# 6_MUX.net
KiCad netlist of a schematic drawn in Altium Designer
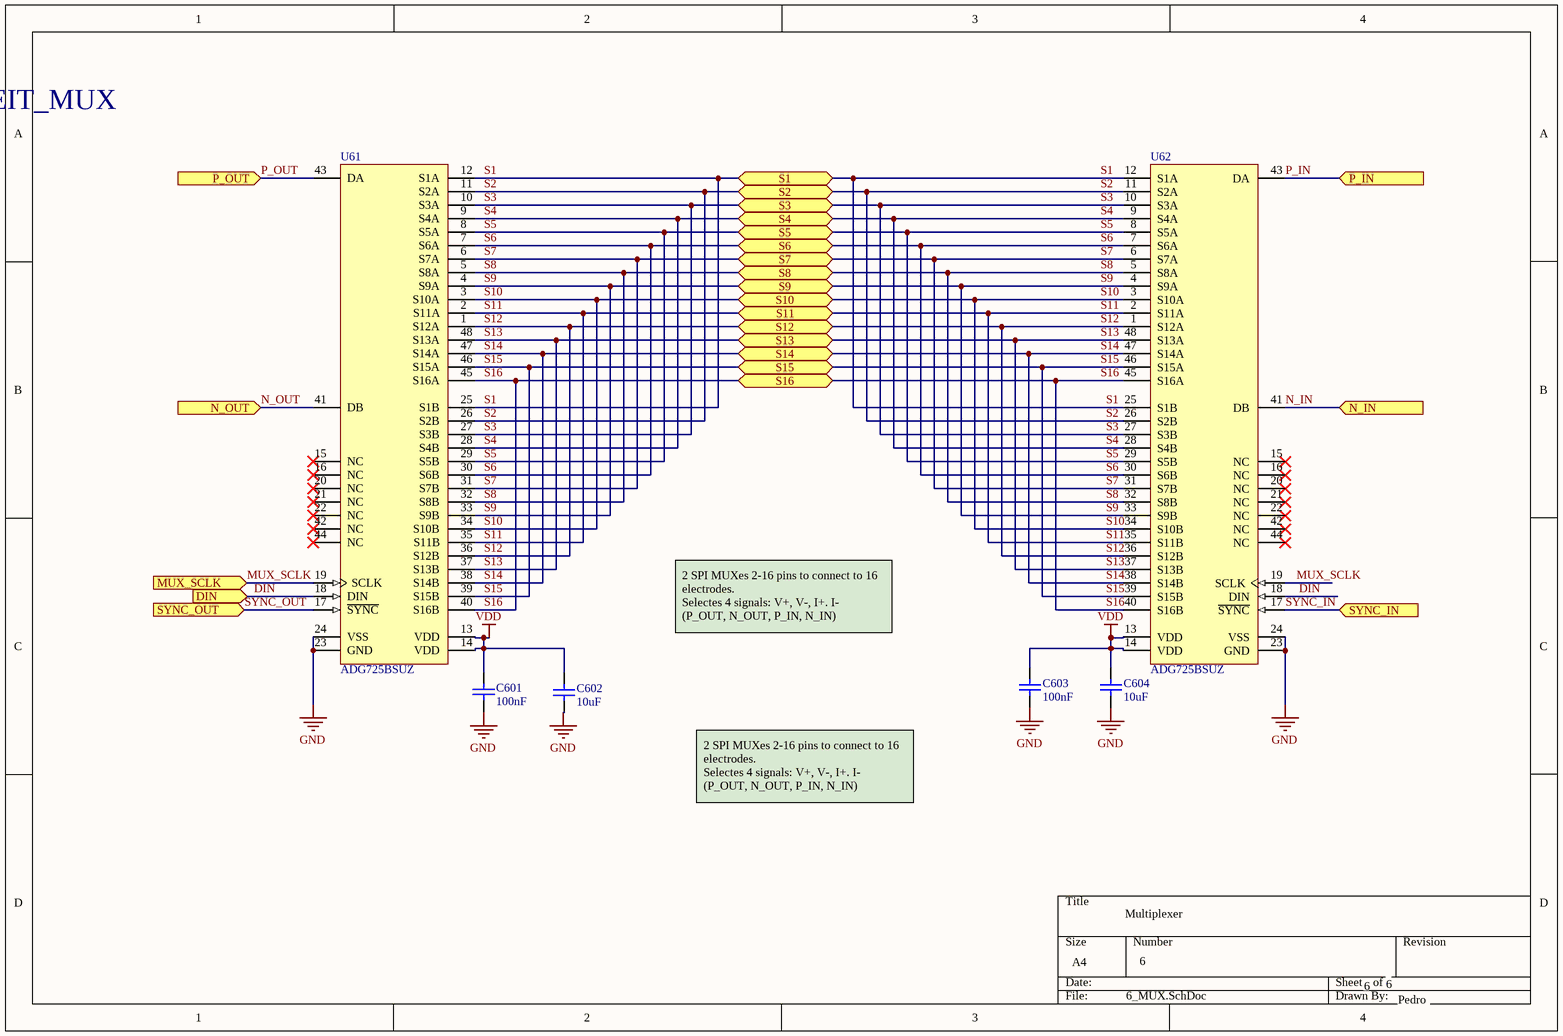
[diagram p0: 6_MUX.SchDoc]

(export (version "E")
  (design (tool "Eeschema 10.0.6"))
  (components
    (comp (ref "C601")
      (value "100nF")
      (footprint "CAPC1005X55X30LL05T10")
      (description "generic")
      (libsource (lib "RPI_EIT_SchLib") (part "Capacitor"))
    )
    (comp (ref "C602")
      (value "10uF")
      (footprint "FP-C0603C-CF-IPC_A")
      (description "generic")
      (libsource (lib "RPI_EIT_SchLib") (part "Capacitor"))
    )
    (comp (ref "C603")
      (value "100nF")
      (footprint "CAPC1005X55X30LL05T10")
      (description "generic")
      (libsource (lib "RPI_EIT_SchLib") (part "Capacitor"))
    )
    (comp (ref "C604")
      (value "10uF")
      (footprint "FP-C0603C-CF-IPC_A")
      (description "generic")
      (libsource (lib "RPI_EIT_SchLib") (part "Capacitor"))
    )
    (comp (ref "U61")
      (value "ADG725BSUZ")
      (footprint "ADI-SU-48_N")
      (fields (field (name "MANUFACTURER") "Analog Devices"))
      (libsource (lib "RPI_EIT_SchLib") (part "ADI-ADG725-SU-48"))
    )
    (comp (ref "U62")
      (value "ADG725BSUZ")
      (footprint "ADI-SU-48_N")
      (fields (field (name "MANUFACTURER") "Analog Devices"))
      (libsource (lib "") (part "ADI-ADG725-SU-48_1"))
    )
  )
  (nets
    (net (code "1") (name "/DIN") (class "Default")
      (node (ref "U61") (pin "18") (pinfunction "DIN_18") (pintype "input"))
      (node (ref "U62") (pin "18") (pinfunction "DIN_18") (pintype "input"))
    )
    (net (code "2") (name "/MUX_SCLK") (class "Default")
      (node (ref "U61") (pin "19") (pinfunction "SCLK_19") (pintype "input"))
      (node (ref "U62") (pin "19") (pinfunction "SCLK_19") (pintype "input"))
    )
    (net (code "3") (name "/N_IN") (class "Default")
      (node (ref "U62") (pin "41") (pinfunction "DB_41") (pintype "passive"))
    )
    (net (code "4") (name "/N_OUT") (class "Default")
      (node (ref "U61") (pin "41") (pinfunction "DB_41") (pintype "passive"))
    )
    (net (code "5") (name "/P_IN") (class "Default")
      (node (ref "U62") (pin "43") (pinfunction "DA_43") (pintype "passive"))
    )
    (net (code "6") (name "/P_OUT") (class "Default")
      (node (ref "U61") (pin "43") (pinfunction "DA_43") (pintype "passive"))
    )
    (net (code "7") (name "/S1") (class "Default")
      (node (ref "U61") (pin "12") (pinfunction "S1A_12") (pintype "passive"))
      (node (ref "U61") (pin "25") (pinfunction "S1B_25") (pintype "passive"))
      (node (ref "U62") (pin "12") (pinfunction "S1A_12") (pintype "passive"))
      (node (ref "U62") (pin "25") (pinfunction "S1B_25") (pintype "passive"))
    )
    (net (code "8") (name "/S2") (class "Default")
      (node (ref "U61") (pin "11") (pinfunction "S2A_11") (pintype "passive"))
      (node (ref "U61") (pin "26") (pinfunction "S2B_26") (pintype "passive"))
      (node (ref "U62") (pin "11") (pinfunction "S2A_11") (pintype "passive"))
      (node (ref "U62") (pin "26") (pinfunction "S2B_26") (pintype "passive"))
    )
    (net (code "9") (name "/S3") (class "Default")
      (node (ref "U61") (pin "10") (pinfunction "S3A_10") (pintype "passive"))
      (node (ref "U61") (pin "27") (pinfunction "S3B_27") (pintype "passive"))
      (node (ref "U62") (pin "10") (pinfunction "S3A_10") (pintype "passive"))
      (node (ref "U62") (pin "27") (pinfunction "S3B_27") (pintype "passive"))
    )
    (net (code "10") (name "/S4") (class "Default")
      (node (ref "U61") (pin "28") (pinfunction "S4B_28") (pintype "passive"))
      (node (ref "U61") (pin "9") (pinfunction "S4A_9") (pintype "passive"))
      (node (ref "U62") (pin "28") (pinfunction "S4B_28") (pintype "passive"))
      (node (ref "U62") (pin "9") (pinfunction "S4A_9") (pintype "passive"))
    )
    (net (code "11") (name "/S5") (class "Default")
      (node (ref "U61") (pin "29") (pinfunction "S5B_29") (pintype "passive"))
      (node (ref "U61") (pin "8") (pinfunction "S5A_8") (pintype "passive"))
      (node (ref "U62") (pin "29") (pinfunction "S5B_29") (pintype "passive"))
      (node (ref "U62") (pin "8") (pinfunction "S5A_8") (pintype "passive"))
    )
    (net (code "12") (name "/S6") (class "Default")
      (node (ref "U61") (pin "30") (pinfunction "S6B_30") (pintype "passive"))
      (node (ref "U61") (pin "7") (pinfunction "S6A_7") (pintype "passive"))
      (node (ref "U62") (pin "30") (pinfunction "S6B_30") (pintype "passive"))
      (node (ref "U62") (pin "7") (pinfunction "S6A_7") (pintype "passive"))
    )
    (net (code "13") (name "/S7") (class "Default")
      (node (ref "U61") (pin "31") (pinfunction "S7B_31") (pintype "passive"))
      (node (ref "U61") (pin "6") (pinfunction "S7A_6") (pintype "passive"))
      (node (ref "U62") (pin "31") (pinfunction "S7B_31") (pintype "passive"))
      (node (ref "U62") (pin "6") (pinfunction "S7A_6") (pintype "passive"))
    )
    (net (code "14") (name "/S8") (class "Default")
      (node (ref "U61") (pin "32") (pinfunction "S8B_32") (pintype "passive"))
      (node (ref "U61") (pin "5") (pinfunction "S8A_5") (pintype "passive"))
      (node (ref "U62") (pin "32") (pinfunction "S8B_32") (pintype "passive"))
      (node (ref "U62") (pin "5") (pinfunction "S8A_5") (pintype "passive"))
    )
    (net (code "15") (name "/S9") (class "Default")
      (node (ref "U61") (pin "33") (pinfunction "S9B_33") (pintype "passive"))
      (node (ref "U61") (pin "4") (pinfunction "S9A_4") (pintype "passive"))
      (node (ref "U62") (pin "33") (pinfunction "S9B_33") (pintype "passive"))
      (node (ref "U62") (pin "4") (pinfunction "S9A_4") (pintype "passive"))
    )
    (net (code "16") (name "/S10") (class "Default")
      (node (ref "U61") (pin "3") (pinfunction "S10A_3") (pintype "passive"))
      (node (ref "U61") (pin "34") (pinfunction "S10B_34") (pintype "passive"))
      (node (ref "U62") (pin "3") (pinfunction "S10A_3") (pintype "passive"))
      (node (ref "U62") (pin "34") (pinfunction "S10B_34") (pintype "passive"))
    )
    (net (code "17") (name "/S11") (class "Default")
      (node (ref "U61") (pin "2") (pinfunction "S11A_2") (pintype "passive"))
      (node (ref "U61") (pin "35") (pinfunction "S11B_35") (pintype "passive"))
      (node (ref "U62") (pin "2") (pinfunction "S11A_2") (pintype "passive"))
      (node (ref "U62") (pin "35") (pinfunction "S11B_35") (pintype "passive"))
    )
    (net (code "18") (name "/S12") (class "Default")
      (node (ref "U61") (pin "1") (pinfunction "S12A_1") (pintype "passive"))
      (node (ref "U61") (pin "36") (pinfunction "S12B_36") (pintype "passive"))
      (node (ref "U62") (pin "1") (pinfunction "S12A_1") (pintype "passive"))
      (node (ref "U62") (pin "36") (pinfunction "S12B_36") (pintype "passive"))
    )
    (net (code "19") (name "/S13") (class "Default")
      (node (ref "U61") (pin "37") (pinfunction "S13B_37") (pintype "passive"))
      (node (ref "U61") (pin "48") (pinfunction "S13A_48") (pintype "passive"))
      (node (ref "U62") (pin "37") (pinfunction "S13B_37") (pintype "passive"))
      (node (ref "U62") (pin "48") (pinfunction "S13A_48") (pintype "passive"))
    )
    (net (code "20") (name "/S14") (class "Default")
      (node (ref "U61") (pin "38") (pinfunction "S14B_38") (pintype "passive"))
      (node (ref "U61") (pin "47") (pinfunction "S14A_47") (pintype "passive"))
      (node (ref "U62") (pin "38") (pinfunction "S14B_38") (pintype "passive"))
      (node (ref "U62") (pin "47") (pinfunction "S14A_47") (pintype "passive"))
    )
    (net (code "21") (name "/S15") (class "Default")
      (node (ref "U61") (pin "39") (pinfunction "S15B_39") (pintype "passive"))
      (node (ref "U61") (pin "46") (pinfunction "S15A_46") (pintype "passive"))
      (node (ref "U62") (pin "39") (pinfunction "S15B_39") (pintype "passive"))
      (node (ref "U62") (pin "46") (pinfunction "S15A_46") (pintype "passive"))
    )
    (net (code "22") (name "/S16") (class "Default")
      (node (ref "U61") (pin "40") (pinfunction "S16B_40") (pintype "passive"))
      (node (ref "U61") (pin "45") (pinfunction "S16A_45") (pintype "passive"))
      (node (ref "U62") (pin "40") (pinfunction "S16B_40") (pintype "passive"))
      (node (ref "U62") (pin "45") (pinfunction "S16A_45") (pintype "passive"))
    )
    (net (code "23") (name "/SYNC_IN") (class "Default")
      (node (ref "U62") (pin "17") (pinfunction "~{SYNC}_17") (pintype "input"))
    )
    (net (code "24") (name "/SYNC_OUT") (class "Default")
      (node (ref "U61") (pin "17") (pinfunction "~{SYNC}_17") (pintype "input"))
    )
    (net (code "25") (name "GND") (class "Default")
      (node (ref "C601") (pin "2") (pinfunction "2_2") (pintype "passive"))
      (node (ref "C602") (pin "2") (pinfunction "2_2") (pintype "passive"))
      (node (ref "C603") (pin "2") (pinfunction "2_2") (pintype "passive"))
      (node (ref "C604") (pin "2") (pinfunction "2_2") (pintype "passive"))
      (node (ref "U61") (pin "23") (pinfunction "GND_23") (pintype "power_in"))
      (node (ref "U61") (pin "24") (pinfunction "VSS_24") (pintype "power_in"))
      (node (ref "U62") (pin "23") (pinfunction "GND_23") (pintype "power_in"))
      (node (ref "U62") (pin "24") (pinfunction "VSS_24") (pintype "power_in"))
    )
    (net (code "26") (name "VDD") (class "Default")
      (node (ref "C601") (pin "1") (pinfunction "1_1") (pintype "passive"))
      (node (ref "C602") (pin "1") (pinfunction "1_1") (pintype "passive"))
      (node (ref "C603") (pin "1") (pinfunction "1_1") (pintype "passive"))
      (node (ref "C604") (pin "1") (pinfunction "1_1") (pintype "passive"))
      (node (ref "U61") (pin "13") (pinfunction "VDD_13") (pintype "power_in"))
      (node (ref "U61") (pin "14") (pinfunction "VDD_14") (pintype "power_in"))
      (node (ref "U62") (pin "13") (pinfunction "VDD_13") (pintype "power_in"))
      (node (ref "U62") (pin "14") (pinfunction "VDD_14") (pintype "power_in"))
    )
    (net (code "27") (name "unconnected-(U61-NC-Pad15)") (class "Default")
      (node (ref "U61") (pin "15") (pinfunction "NC_15") (pintype "passive+no_connect"))
    )
    (net (code "28") (name "unconnected-(U61-NC-Pad16)") (class "Default")
      (node (ref "U61") (pin "16") (pinfunction "NC_16") (pintype "passive+no_connect"))
    )
    (net (code "29") (name "unconnected-(U61-NC-Pad20)") (class "Default")
      (node (ref "U61") (pin "20") (pinfunction "NC_20") (pintype "passive+no_connect"))
    )
    (net (code "30") (name "unconnected-(U61-NC-Pad21)") (class "Default")
      (node (ref "U61") (pin "21") (pinfunction "NC_21") (pintype "passive+no_connect"))
    )
    (net (code "31") (name "unconnected-(U61-NC-Pad22)") (class "Default")
      (node (ref "U61") (pin "22") (pinfunction "NC_22") (pintype "passive+no_connect"))
    )
    (net (code "32") (name "unconnected-(U61-NC-Pad42)") (class "Default")
      (node (ref "U61") (pin "42") (pinfunction "NC_42") (pintype "passive+no_connect"))
    )
    (net (code "33") (name "unconnected-(U61-NC-Pad44)") (class "Default")
      (node (ref "U61") (pin "44") (pinfunction "NC_44") (pintype "passive+no_connect"))
    )
    (net (code "34") (name "unconnected-(U62-NC-Pad15)") (class "Default")
      (node (ref "U62") (pin "15") (pinfunction "NC_15") (pintype "passive+no_connect"))
    )
    (net (code "35") (name "unconnected-(U62-NC-Pad16)") (class "Default")
      (node (ref "U62") (pin "16") (pinfunction "NC_16") (pintype "passive+no_connect"))
    )
    (net (code "36") (name "unconnected-(U62-NC-Pad20)") (class "Default")
      (node (ref "U62") (pin "20") (pinfunction "NC_20") (pintype "passive+no_connect"))
    )
    (net (code "37") (name "unconnected-(U62-NC-Pad21)") (class "Default")
      (node (ref "U62") (pin "21") (pinfunction "NC_21") (pintype "passive+no_connect"))
    )
    (net (code "38") (name "unconnected-(U62-NC-Pad22)") (class "Default")
      (node (ref "U62") (pin "22") (pinfunction "NC_22") (pintype "passive+no_connect"))
    )
    (net (code "39") (name "unconnected-(U62-NC-Pad42)") (class "Default")
      (node (ref "U62") (pin "42") (pinfunction "NC_42") (pintype "passive+no_connect"))
    )
    (net (code "40") (name "unconnected-(U62-NC-Pad44)") (class "Default")
      (node (ref "U62") (pin "44") (pinfunction "NC_44") (pintype "passive+no_connect"))
    )
  )
)
